# jtag.net
KiCad netlist of a schematic drawn in Altium Designer
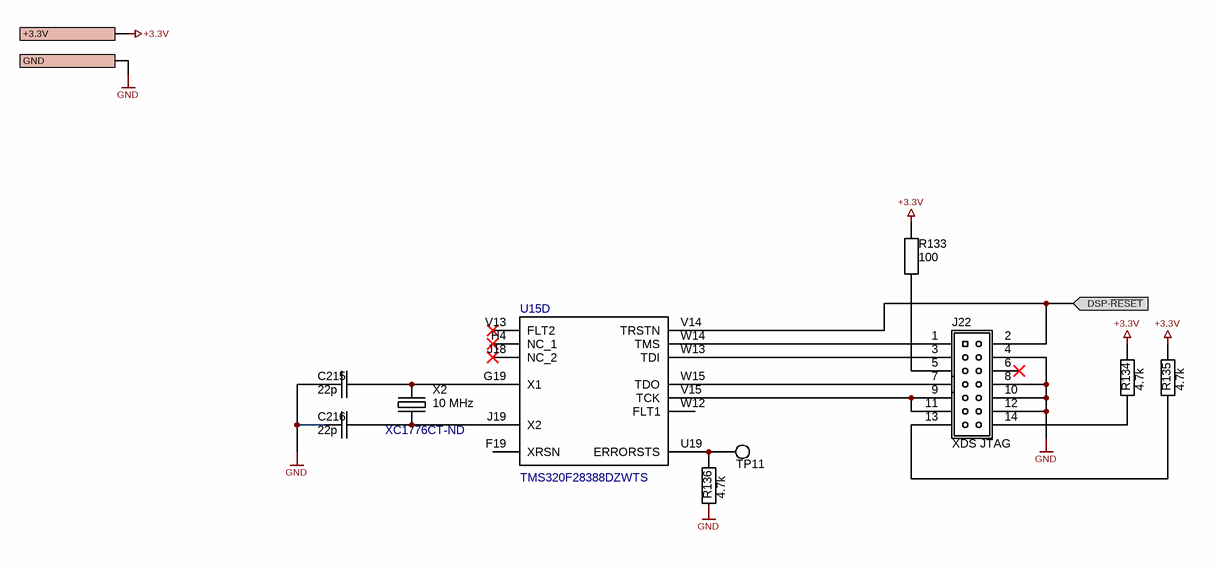
[diagram p0: jtag.SchDoc]

(export (version "E")
  (design (tool "Eeschema 10.0.6"))
  (components
    (comp (ref "C215")
      (value "22p")
      (footprint "SM/C0402")
      (description "22 pF ±2% 50V Ceramic Capacitor C0G, NP0 0402 (1005 Metric)")
      (fields (field (name "VOLTAGE") "50V"))
      (libsource (lib "kalios") (part "C"))
    )
    (comp (ref "C216")
      (value "22p")
      (footprint "SM/C0402")
      (description "22 pF ±2% 50V Ceramic Capacitor C0G, NP0 0402 (1005 Metric)")
      (fields (field (name "VOLTAGE") "50V"))
      (libsource (lib "kalios") (part "C"))
    )
    (comp (ref "J22")
      (value "XDS JTAG")
      (footprint "SAMTEC_SHF-107-01-L-D-SM")
      (libsource (lib "kalios") (part "CONN 14POS"))
    )
    (comp (ref "R133")
      (value "100")
      (footprint "SM/R0402")
      (description "100 Ohms ±1% 0.063W, 1/16W Chip Resistor 0402 (1005 Metric) Moisture Resistant Thick Film")
      (libsource (lib "kalios") (part "R"))
    )
    (comp (ref "R134")
      (value "4.7k")
      (footprint "SM/R0402")
      (description "4.7 kOhms ±5% 0.063W, 1/16W Chip Resistor 0402 (1005 Metric) Moisture Resistant Thick Film")
      (libsource (lib "") (part "R_1"))
    )
    (comp (ref "R135")
      (value "4.7k")
      (footprint "SM/R0402")
      (description "4.7 kOhms ±5% 0.063W, 1/16W Chip Resistor 0402 (1005 Metric) Moisture Resistant Thick Film")
      (libsource (lib "") (part "R_1"))
    )
    (comp (ref "R136")
      (value "4.7k")
      (footprint "SM/R0402")
      (description "4.7 kOhms ±5% 0.063W, 1/16W Chip Resistor 0402 (1005 Metric) Moisture Resistant Thick Film")
      (libsource (lib "") (part "R_1"))
    )
    (comp (ref "TP11")
      (value "RCUCTE")
      (footprint "TP/RCUCT")
      (description "PC Test Point Plating Surface Mount Mounting Type")
      (libsource (lib "kalios") (part "TP"))
    )
    (comp (ref "U15")
      (value "TMS320F28388DZWTS")
      (footprint "SamacSys:BGA337C80P19X19_1600X1600X140")
      (description "Integrated Circuit")
      (libsource (lib "kalios") (part "TMS320F28388DZWTS"))
    )
    (comp (ref "X2")
      (value "10 MHz")
      (footprint "XTAL-ECS-160-20-3X-TR")
      (fields (field (name "SUPPLIER PART NUMBER 1") "XC1776CT-ND"))
      (libsource (lib "kalios") (part "XTAL"))
    )
  )
  (nets
    (net (code "1") (name "+3.3V") (class "Default")
      (node (ref "R133") (pin "2") (pintype "passive"))
      (node (ref "R134") (pin "1") (pintype "passive"))
      (node (ref "R135") (pin "1") (pintype "passive"))
    )
    (net (code "2") (name "/DSP-~{RESET}") (class "Default")
      (node (ref "J22") (pin "2") (pinfunction "2_2") (pintype "passive"))
      (node (ref "U15") (pin "V14") (pinfunction "TRSTN_V14") (pintype "passive"))
    )
    (net (code "3") (name "GND") (class "Default")
      (node (ref "C215") (pin "2") (pintype "passive"))
      (node (ref "C216") (pin "2") (pintype "passive"))
      (node (ref "J22") (pin "10") (pinfunction "10_10") (pintype "passive"))
      (node (ref "J22") (pin "12") (pinfunction "12_12") (pintype "passive"))
      (node (ref "J22") (pin "4") (pinfunction "4_4") (pintype "passive"))
      (node (ref "J22") (pin "8") (pinfunction "8_8") (pintype "passive"))
      (node (ref "R136") (pin "2") (pintype "passive"))
    )
    (net (code "4") (name "Net-(J22-Pad5)") (class "Default")
      (node (ref "J22") (pin "5") (pinfunction "5_5") (pintype "passive"))
      (node (ref "R133") (pin "1") (pintype "passive"))
    )
    (net (code "5") (name "Net-(J22-Pad13)") (class "Default")
      (node (ref "J22") (pin "13") (pinfunction "13_13") (pintype "passive"))
      (node (ref "R135") (pin "2") (pintype "passive"))
    )
    (net (code "6") (name "Net-(J22-Pad14)") (class "Default")
      (node (ref "J22") (pin "14") (pinfunction "14_14") (pintype "passive"))
      (node (ref "R134") (pin "2") (pintype "passive"))
    )
    (net (code "7") (name "Net-(U15D-ERRORSTS)") (class "Default")
      (node (ref "R136") (pin "1") (pintype "passive"))
      (node (ref "TP11") (pin "1") (pinfunction "1_1") (pintype "passive"))
      (node (ref "U15") (pin "U19") (pinfunction "ERRORSTS_U19") (pintype "passive"))
    )
    (net (code "8") (name "Net-(U15D-TCK)") (class "Default")
      (node (ref "J22") (pin "11") (pinfunction "11_11") (pintype "passive"))
      (node (ref "J22") (pin "9") (pinfunction "9_9") (pintype "passive"))
      (node (ref "U15") (pin "V15") (pinfunction "TCK_V15") (pintype "passive"))
    )
    (net (code "9") (name "Net-(U15D-TDI)") (class "Default")
      (node (ref "J22") (pin "3") (pinfunction "3_3") (pintype "passive"))
      (node (ref "U15") (pin "W13") (pinfunction "TDI_W13") (pintype "passive"))
    )
    (net (code "10") (name "Net-(U15D-TDO)") (class "Default")
      (node (ref "J22") (pin "7") (pinfunction "7_7") (pintype "passive"))
      (node (ref "U15") (pin "W15") (pinfunction "TDO_W15") (pintype "passive"))
    )
    (net (code "11") (name "Net-(U15D-TMS)") (class "Default")
      (node (ref "J22") (pin "1") (pinfunction "1_1") (pintype "passive"))
      (node (ref "U15") (pin "W14") (pinfunction "TMS_W14") (pintype "passive"))
    )
    (net (code "12") (name "Net-(U15D-X1)") (class "Default")
      (node (ref "C215") (pin "1") (pintype "passive"))
      (node (ref "U15") (pin "G19") (pinfunction "X1_G19") (pintype "passive"))
      (node (ref "X2") (pin "2") (pinfunction "2_2") (pintype "passive"))
    )
    (net (code "13") (name "Net-(U15D-X2)") (class "Default")
      (node (ref "C216") (pin "1") (pintype "passive"))
      (node (ref "U15") (pin "J19") (pinfunction "X2_J19") (pintype "passive"))
      (node (ref "X2") (pin "1") (pinfunction "1_1") (pintype "passive"))
    )
    (net (code "14") (name "unconnected-(J22-Pad6)") (class "Default")
      (node (ref "J22") (pin "6") (pinfunction "6_6") (pintype "passive+no_connect"))
    )
    (net (code "15") (name "unconnected-(U15D-FLT1-PadW12)") (class "Default")
      (node (ref "U15") (pin "W12") (pinfunction "FLT1_W12") (pintype "passive"))
    )
    (net (code "16") (name "unconnected-(U15D-FLT2-PadV13)") (class "Default")
      (node (ref "U15") (pin "V13") (pinfunction "FLT2_V13") (pintype "passive+no_connect"))
    )
    (net (code "17") (name "unconnected-(U15D-NC_1-PadH4)") (class "Default")
      (node (ref "U15") (pin "H4") (pinfunction "NC_1_H4") (pintype "passive+no_connect"))
    )
    (net (code "18") (name "unconnected-(U15D-NC_2-PadJ18)") (class "Default")
      (node (ref "U15") (pin "J18") (pinfunction "NC_2_J18") (pintype "passive+no_connect"))
    )
    (net (code "19") (name "unconnected-(U15D-XRSN-PadF19)") (class "Default")
      (node (ref "U15") (pin "F19") (pinfunction "XRSN_F19") (pintype "passive"))
    )
  )
)
